# E32_Lora_T30S433MHz.net
KiCad netlist of a schematic drawn in Altium Designer
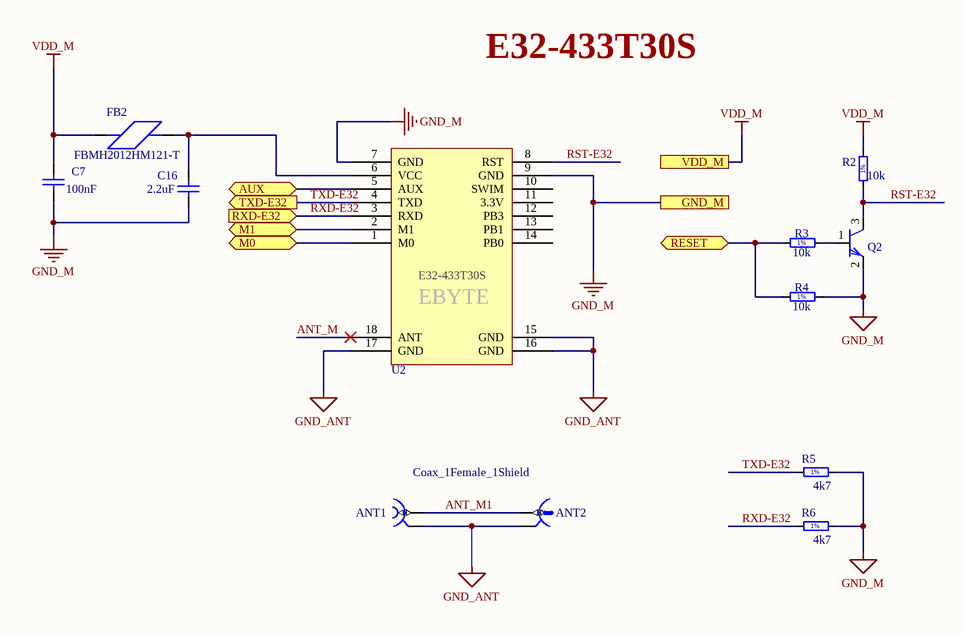
[diagram p0: E32_Lora_T30S433MHz.SchDoc]

(export (version "E")
  (design (tool "Eeschema 10.0.6"))
  (components
    (comp (ref "ANT1")
      (value "Coax_1Female_1Shield")
      (footprint "HUBER-SUHNER_85 SMA-50-0-101/111 NE")
      (fields
        (field (name "PART NUMBER") "HUBER-SUHNER_85_SMA-50-0-101/111_NE")
        (field (name "MANUFACTURER") "HUBER+SUHNER")
        (field (name "MANUFACTURER PART NUMBER") "85_SMA-50-0-101/111_NE")
        (field (name "AUTHOR") "CERN DEM JLC")
      )
      (libsource (lib "Connectors") (part "Coax_1Female_1Shield"))
    )
    (comp (ref "ANT2")
      (value "U.FL")
      (footprint "HIROSE_U.FL-R-SMT-1(10)")
      (fields
        (field (name "PART NUMBER") "HIROSE_U.FL-R-SMT-1(10)")
        (field (name "MANUFACTURER") "HIROSE (HRS)")
        (field (name "MANUFACTURER PART NUMBER") "U.FL-R-SMT-1(10)")
        (field (name "AUTHOR") "CERN DEM JLC")
      )
      (libsource (lib "Connectors") (part "Coax_1Male_1Shield"))
    )
    (comp (ref "C7")
      (value "100nF")
      (footprint "CAPC1608X87N")
      (description "Non-polarised capacitor")
      (fields
        (field (name "PART NUMBER") "CC0603_100NF_50V_10%_X7R")
        (field (name "VOLTAGE") "50V")
        (field (name "AUTHOR") "CERN DEM JLC")
      )
      (libsource (lib "Capacitors") (part "Capacitor - non polarized"))
    )
    (comp (ref "C16")
      (value "2.2uF")
      (footprint "CAPC1608X87N")
      (description "Non-polarised capacitor")
      (fields
        (field (name "PART NUMBER") "CC0603_2.2UF_16V_10%_X5R")
        (field (name "VOLTAGE") "16V")
        (field (name "AUTHOR") "CERN DEM JLC")
      )
      (libsource (lib "Capacitors") (part "Capacitor - non polarized"))
    )
    (comp (ref "FB2")
      (value "Ferrite bead Case 0805")
      (footprint "CHIP_0805")
      (fields (field (name "MANUFACTURER PART NUMBER") "FBMH2012HM121-T"))
      (libsource (lib "Schlib1") (part "FERRITE_0805"))
    )
    (comp (ref "Q2")
      (value "C1815")
      (footprint "SOT23-3")
      (fields (field (name "PUBLISHER") "Hoang Nguyen"))
      (libsource (lib "alib_pnphien") (part "2SC1815"))
    )
    (comp (ref "R2")
      (value "10k")
      (footprint "RESC1608X55N")
      (description "Resistor - 1%")
      (fields
        (field (name "PART NUMBER") "R0603_4K7_1%_0.1W_100PPM")
        (field (name "POWER") "0.1W")
        (field (name "AUTHOR") "CERN DEM JLC")
      )
      (libsource (lib "") (part "Resistor - 1%_1"))
    )
    (comp (ref "R3")
      (value "10k")
      (footprint "RESC1608X55N")
      (description "Resistor - 1%")
      (fields
        (field (name "PART NUMBER") "R0603_1K_1%_0.1W_100PPM")
        (field (name "POWER") "0.1W")
        (field (name "AUTHOR") "CERN DEM JLC")
      )
      (libsource (lib "") (part "Resistor - 1%_1"))
    )
    (comp (ref "R4")
      (value "10k")
      (footprint "RESC1608X55N")
      (description "Resistor - 1%")
      (fields
        (field (name "PART NUMBER") "R0603_1K_1%_0.1W_100PPM")
        (field (name "POWER") "0.1W")
        (field (name "AUTHOR") "CERN DEM JLC")
      )
      (libsource (lib "Resistors") (part "Resistor - 1%"))
    )
    (comp (ref "R5")
      (value "4k7")
      (footprint "RESC1608X55N")
      (description "Resistor - 1%")
      (fields
        (field (name "PART NUMBER") "R0603_10K_1%_0.1W_100PPM")
        (field (name "POWER") "0.1W")
        (field (name "AUTHOR") "CERN DEM JLC")
      )
      (libsource (lib "") (part "Resistor - 1%_1"))
    )
    (comp (ref "R6")
      (value "4k7")
      (footprint "RESC1608X55N")
      (description "Resistor - 1%")
      (fields
        (field (name "PART NUMBER") "R0603_10K_1%_0.1W_100PPM")
        (field (name "POWER") "0.1W")
        (field (name "AUTHOR") "CERN DEM JLC")
      )
      (libsource (lib "") (part "Resistor - 1%_1"))
    )
    (comp (ref "U2")
      (value "E32-T30S")
      (footprint "E32-T30S")
      (description "Lora Ebyte E32-T30S Module")
      (libsource (lib "alib_pnphien") (part "E32-433T30S"))
    )
  )
  (nets
    (net (code "1") (name "/ANT_M") (class "Default")
      (node (ref "U2") (pin "18") (pinfunction "ANT_18") (pintype "passive+no_connect"))
    )
    (net (code "2") (name "/ANT_M1") (class "Default")
      (node (ref "ANT1") (pin "1") (pinfunction "1_1") (pintype "bidirectional"))
      (node (ref "ANT2") (pin "1") (pinfunction "1_1") (pintype "bidirectional"))
    )
    (net (code "3") (name "/AUX") (class "Default")
      (node (ref "U2") (pin "5") (pinfunction "AUX_5") (pintype "passive"))
    )
    (net (code "4") (name "/M0") (class "Default")
      (node (ref "U2") (pin "1") (pinfunction "M0_1") (pintype "passive"))
    )
    (net (code "5") (name "/M1") (class "Default")
      (node (ref "U2") (pin "2") (pinfunction "M1_2") (pintype "passive"))
    )
    (net (code "6") (name "/RESET") (class "Default")
      (node (ref "R3") (pin "1") (pinfunction "1_1") (pintype "passive"))
      (node (ref "R4") (pin "2") (pinfunction "2_2") (pintype "passive"))
    )
    (net (code "7") (name "/RST-E32") (class "Default")
      (node (ref "Q2") (pin "3") (pinfunction "C_3") (pintype "passive"))
      (node (ref "R2") (pin "1") (pinfunction "1_1") (pintype "passive"))
      (node (ref "U2") (pin "8") (pinfunction "RST_8") (pintype "passive"))
    )
    (net (code "8") (name "/RXD-E32") (class "Default")
      (node (ref "R6") (pin "1") (pinfunction "1_1") (pintype "passive"))
      (node (ref "U2") (pin "3") (pinfunction "RXD_3") (pintype "passive"))
    )
    (net (code "9") (name "/TXD-E32") (class "Default")
      (node (ref "R5") (pin "1") (pinfunction "1_1") (pintype "passive"))
      (node (ref "U2") (pin "4") (pinfunction "TXD_4") (pintype "passive"))
    )
    (net (code "10") (name "GND_ANT") (class "Default")
      (node (ref "ANT1") (pin "2") (pinfunction "2_2") (pintype "power_in"))
      (node (ref "ANT2") (pin "2") (pinfunction "2_2") (pintype "power_in"))
      (node (ref "U2") (pin "15") (pinfunction "GND_15") (pintype "passive"))
      (node (ref "U2") (pin "16") (pinfunction "GND_16") (pintype "passive"))
      (node (ref "U2") (pin "17") (pinfunction "GND_17") (pintype "passive"))
    )
    (net (code "11") (name "GND_M") (class "Default")
      (node (ref "C16") (pin "1") (pinfunction "1_1") (pintype "passive"))
      (node (ref "C7") (pin "1") (pinfunction "1_1") (pintype "passive"))
      (node (ref "Q2") (pin "2") (pinfunction "E_2") (pintype "passive"))
      (node (ref "R4") (pin "1") (pinfunction "1_1") (pintype "passive"))
      (node (ref "R5") (pin "2") (pinfunction "2_2") (pintype "passive"))
      (node (ref "R6") (pin "2") (pinfunction "2_2") (pintype "passive"))
      (node (ref "U2") (pin "7") (pinfunction "GND_7") (pintype "passive"))
      (node (ref "U2") (pin "9") (pinfunction "GND_9") (pintype "passive"))
    )
    (net (code "12") (name "Net-(Q2-B)") (class "Default")
      (node (ref "Q2") (pin "1") (pinfunction "B_1") (pintype "passive"))
      (node (ref "R3") (pin "2") (pinfunction "2_2") (pintype "passive"))
    )
    (net (code "13") (name "Net-(U2-VCC)") (class "Default")
      (node (ref "C16") (pin "2") (pinfunction "2_2") (pintype "passive"))
      (node (ref "FB2") (pin "2") (pinfunction "2_2") (pintype "passive"))
      (node (ref "U2") (pin "6") (pinfunction "VCC_6") (pintype "passive"))
    )
    (net (code "14") (name "VDD_M") (class "Default")
      (node (ref "C7") (pin "2") (pinfunction "2_2") (pintype "passive"))
      (node (ref "FB2") (pin "1") (pinfunction "1_1") (pintype "passive"))
      (node (ref "R2") (pin "2") (pinfunction "2_2") (pintype "passive"))
    )
    (net (code "15") (name "unconnected-(U2-3.3V-Pad11)") (class "Default")
      (node (ref "U2") (pin "11") (pinfunction "3.3V_11") (pintype "passive"))
    )
    (net (code "16") (name "unconnected-(U2-PB0-Pad14)") (class "Default")
      (node (ref "U2") (pin "14") (pinfunction "PB0_14") (pintype "passive"))
    )
    (net (code "17") (name "unconnected-(U2-PB1-Pad13)") (class "Default")
      (node (ref "U2") (pin "13") (pinfunction "PB1_13") (pintype "passive"))
    )
    (net (code "18") (name "unconnected-(U2-PB3-Pad12)") (class "Default")
      (node (ref "U2") (pin "12") (pinfunction "PB3_12") (pintype "passive"))
    )
    (net (code "19") (name "unconnected-(U2-SWIM-Pad10)") (class "Default")
      (node (ref "U2") (pin "10") (pinfunction "SWIM_10") (pintype "passive"))
    )
  )
)
